# spectrometer-breakout-1c2.net
KiCad netlist of a schematic drawn in EAGLE
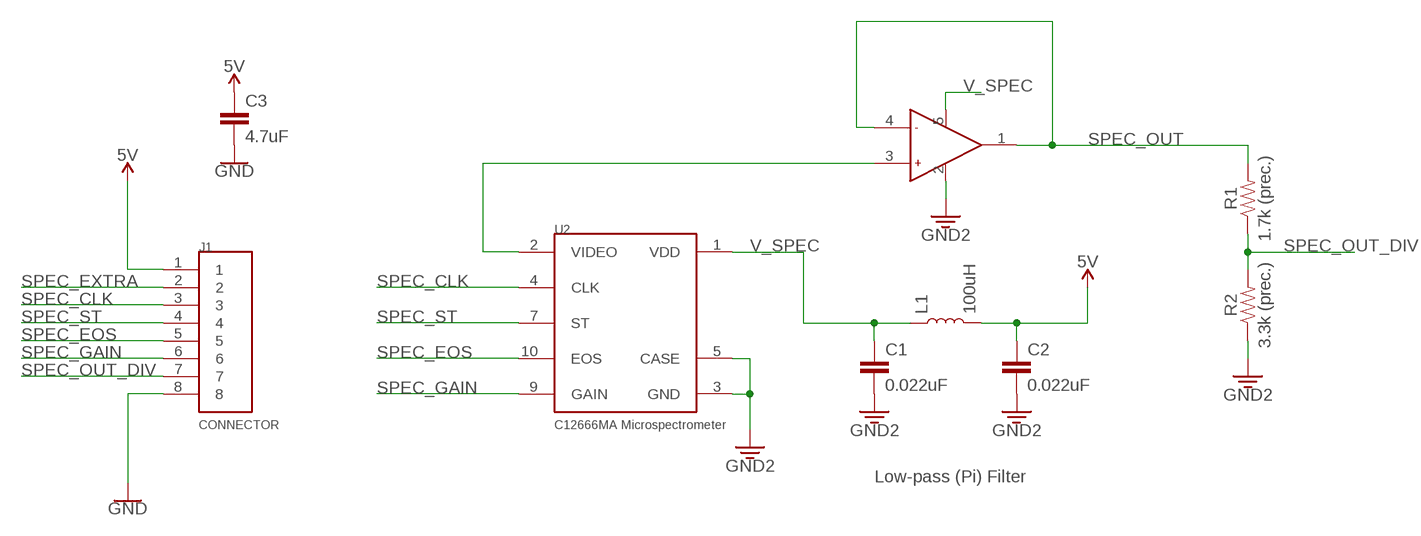
[diagram p0: schematic, sheet 1]

(export (version "E")
  (design (tool "Eeschema 10.0.6"))
  (components
    (comp (ref "C1")
      (value "0.022uF")
      (footprint "eagle-import:0603")
      (libsource (lib "eagle-import") (part "CAP-0603"))
    )
    (comp (ref "C2")
      (value "0.022uF")
      (footprint "eagle-import:0603")
      (libsource (lib "eagle-import") (part "CAP-0603"))
    )
    (comp (ref "C3")
      (value "4.7uF")
      (footprint "eagle-import:0603")
      (libsource (lib "eagle-import") (part "CAP-0603"))
    )
    (comp (ref "J1")
      (value "CON-SM08B-SRSS-TB")
      (footprint "eagle-import:CON-SM08B-SRSS-TB")
      (libsource (lib "eagle-import") (part "CON-SM08B-SRSS-TB"))
    )
    (comp (ref "L1")
      (value "100uH")
      (footprint "eagle-import:0603")
      (libsource (lib "eagle-import") (part "INDUCTORDNP"))
    )
    (comp (ref "R1")
      (value "1.7k (prec.)")
      (footprint "eagle-import:0603")
      (libsource (lib "eagle-import") (part "RESISTOR0603"))
    )
    (comp (ref "R2")
      (value "3.3k (prec.)")
      (footprint "eagle-import:0603")
      (libsource (lib "eagle-import") (part "RESISTOR0603"))
    )
    (comp (ref "U1")
      (value "OPA344NA/250")
      (footprint "eagle-import:SOT3-5")
      (libsource (lib "eagle-import") (part "OPA344NA/250"))
    )
    (comp (ref "U2")
      (value "C12666MA")
      (footprint "eagle-import:C12666MA")
      (libsource (lib "eagle-import") (part "C12666MA"))
    )
  )
  (nets
    (net (code "1") (name "/SPEC_CLK") (class "Default")
      (node (ref "J1") (pin "3") (pinfunction "3_3") (pintype "bidirectional"))
      (node (ref "U2") (pin "4") (pinfunction "CLK_4") (pintype "bidirectional"))
    )
    (net (code "2") (name "/SPEC_EOS") (class "Default")
      (node (ref "J1") (pin "5") (pinfunction "5_5") (pintype "bidirectional"))
      (node (ref "U2") (pin "10") (pinfunction "EOS_10") (pintype "bidirectional"))
    )
    (net (code "3") (name "/SPEC_EXTRA") (class "Default")
      (node (ref "J1") (pin "2") (pinfunction "2_2") (pintype "bidirectional"))
    )
    (net (code "4") (name "/SPEC_GAIN") (class "Default")
      (node (ref "J1") (pin "6") (pinfunction "6_6") (pintype "bidirectional"))
      (node (ref "U2") (pin "9") (pinfunction "GAIN_9") (pintype "bidirectional"))
    )
    (net (code "5") (name "/SPEC_OUT") (class "Default")
      (node (ref "R1") (pin "2") (pinfunction "2_2") (pintype "passive"))
      (node (ref "U1") (pin "1") (pinfunction "OUT_1") (pintype "bidirectional"))
      (node (ref "U1") (pin "4") (pinfunction "-_4") (pintype "bidirectional"))
    )
    (net (code "6") (name "/SPEC_OUT_DIV") (class "Default")
      (node (ref "J1") (pin "7") (pinfunction "7_7") (pintype "bidirectional"))
      (node (ref "R1") (pin "1") (pinfunction "1_1") (pintype "passive"))
      (node (ref "R2") (pin "2") (pinfunction "2_2") (pintype "passive"))
    )
    (net (code "7") (name "/SPEC_ST") (class "Default")
      (node (ref "J1") (pin "4") (pinfunction "4_4") (pintype "bidirectional"))
      (node (ref "U2") (pin "7") (pinfunction "ST_7") (pintype "bidirectional"))
    )
    (net (code "8") (name "/V_SPEC") (class "Default")
      (node (ref "C1") (pin "1") (pinfunction "1_1") (pintype "passive"))
      (node (ref "L1") (pin "1") (pinfunction "1_1") (pintype "passive"))
      (node (ref "U1") (pin "5") (pinfunction "VCC_5") (pintype "bidirectional"))
      (node (ref "U2") (pin "1") (pinfunction "VDD_1") (pintype "bidirectional"))
    )
    (net (code "9") (name "5V") (class "Default")
      (node (ref "C2") (pin "1") (pinfunction "1_1") (pintype "passive"))
      (node (ref "C3") (pin "1") (pinfunction "1_1") (pintype "passive"))
      (node (ref "J1") (pin "1") (pinfunction "1_1") (pintype "bidirectional"))
      (node (ref "L1") (pin "2") (pinfunction "2_2") (pintype "passive"))
    )
    (net (code "10") (name "GND") (class "Default")
      (node (ref "C1") (pin "2") (pinfunction "2_2") (pintype "passive"))
      (node (ref "C2") (pin "2") (pinfunction "2_2") (pintype "passive"))
      (node (ref "C3") (pin "2") (pinfunction "2_2") (pintype "passive"))
      (node (ref "J1") (pin "8") (pinfunction "8_8") (pintype "bidirectional"))
      (node (ref "R2") (pin "1") (pinfunction "1_1") (pintype "passive"))
      (node (ref "U1") (pin "2") (pinfunction "GND_2") (pintype "bidirectional"))
      (node (ref "U2") (pin "3") (pinfunction "GND_3") (pintype "bidirectional"))
      (node (ref "U2") (pin "5") (pinfunction "CASE_5") (pintype "bidirectional"))
    )
    (net (code "11") (name "Net-(U1-+)") (class "Default")
      (node (ref "U1") (pin "3") (pinfunction "+_3") (pintype "bidirectional"))
      (node (ref "U2") (pin "2") (pinfunction "VIDEO_2") (pintype "bidirectional"))
    )
  )
)
